# onduleur.net
KiCad netlist of a schematic drawn in Altium Designer
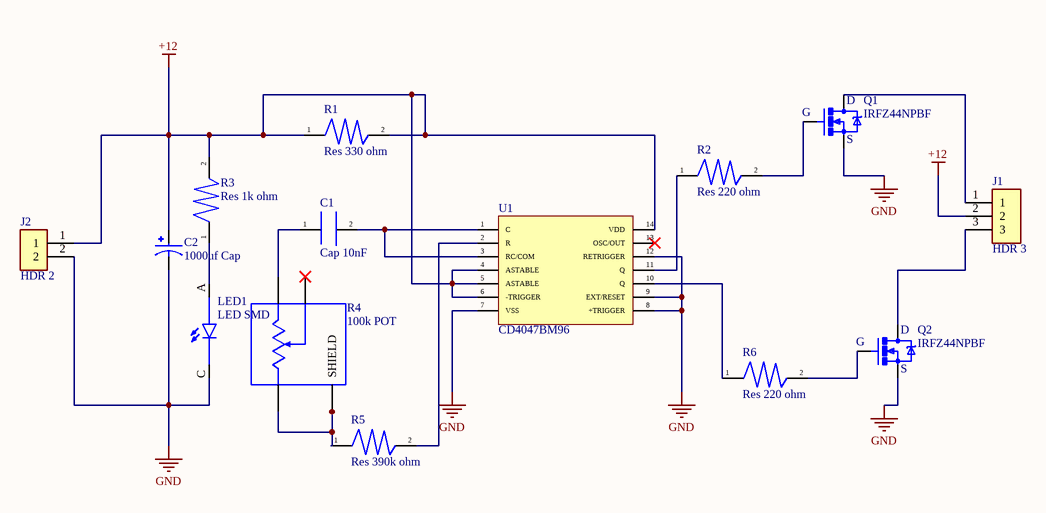
[diagram p0: onduleur.SchDoc]

(export (version "E")
  (design (tool "Eeschema 10.0.6"))
  (components
    (comp (ref "C1")
      (value "Cap 10nF")
      (footprint "C0805 10nf")
      (description "0805 330 nF 25 V -20 / +80 % Tolerance Y5V SMT Multilayer Ceramic Capacitor")
      (fields
        (field (name "MANUFACTURER") "Kyocera AVX")
        (field (name "MANUFACTURER PART NUMBER") "08053G334ZAT2A")
      )
      (libsource (lib "ONDULEUR") (part "Cap 10nF"))
    )
    (comp (ref "C2")
      (value "1000uf Cap")
      (footprint "Cap 1000uf")
      (description "Cap Aluminum 1000uF 50V 20% (12.5 X 25mm) Radial 5mm 950mA 2000 hr 105°C Ammo Pack")
      (fields
        (field (name "MANUFACTURER") "Panasonic")
        (field (name "MANUFACTURER PART NUMBER") "EEU-HD1H102B")
      )
      (libsource (lib "ONDULEUR") (part "1000uf Cap"))
    )
    (comp (ref "J1")
      (value "HDR 3")
      (footprint "HDR 3")
      (description "3 Position Wire to Board Terminal Block Horizontal with Board 0.150\" (3.81mm) Through Hole")
      (fields
        (field (name "MANUFACTURER") "TE Connectivity")
        (field (name "MANUFACTURER PART NUMBER") "284392-3")
      )
      (libsource (lib "ONDULEUR") (part "HDR 3"))
    )
    (comp (ref "J2")
      (value "HDR 2")
      (footprint "HDR 2")
      (description "Conn Terminal Block 2 POS 5.08mm Solder ST Thru-Hole 17.5A/Contact")
      (fields
        (field (name "MANUFACTURER") "TE Connectivity")
        (field (name "MANUFACTURER PART NUMBER") "282841-2")
      )
      (libsource (lib "ONDULEUR") (part "HDR 2"))
    )
    (comp (ref "LED1")
      (value "LED SMD")
      (footprint "LED")
      (description "LED RED CLEAR 1206 SMD")
      (fields
        (field (name "MANUFACTURER") "Vishay Lite-On")
        (field (name "MANUFACTURER PART NUMBER") "LTST-C230KRKT")
      )
      (libsource (lib "ONDULEUR") (part "LED SMD"))
    )
    (comp (ref "Q1")
      (value "IRFZ44NPBF")
      (footprint "IRF")
      (description "N沟道 VDS=55V VGS=±20V ID=49A")
      (fields (field (name "MANUFACTURER") "Infineon"))
      (libsource (lib "ONDULEUR") (part "IRFZ44NPBF"))
    )
    (comp (ref "Q2")
      (value "IRFZ44NPBF")
      (footprint "IRF")
      (description "N沟道 VDS=55V VGS=±20V ID=49A")
      (fields (field (name "MANUFACTURER") "Infineon"))
      (libsource (lib "ONDULEUR") (part "IRFZ44NPBF"))
    )
    (comp (ref "R1")
      (value "Res 330 ohm")
      (footprint "R2010 330 ohm")
      (description "Res Thick Film 2010 330 Ohm 1% 1W ±100ppm/°C Molded SMD SMD Paper T/R")
      (fields
        (field (name "MANUFACTURER") "Stackpole Electronics")
        (field (name "MANUFACTURER PART NUMBER") "RMCP2010FT330R")
      )
      (libsource (lib "ONDULEUR") (part "Res 330 ohm"))
    )
    (comp (ref "R2")
      (value "Res 220 ohm")
      (footprint "R2512 220ohm")
      (description "Res Thick Film 2512 220 Ohm 1% 1W ±100ppm/°C Pad SMD T/R")
      (fields
        (field (name "MANUFACTURER") "Yageo")
        (field (name "MANUFACTURER PART NUMBER") "RC2512FK-07220RL")
      )
      (libsource (lib "ONDULEUR") (part "Res 220 ohm"))
    )
    (comp (ref "R3")
      (value "Res 1k ohm")
      (footprint "R2512 390k")
      (description "贴片电阻 1KΩ 1KΩ ±5% 1W 2512")
      (fields
        (field (name "MANUFACTURER") "Yageo")
        (field (name "MANUFACTURER PART NUMBER") "RC2512JK-071KL")
      )
      (libsource (lib "ONDULEUR") (part "Res 1k ohm"))
    )
    (comp (ref "R4")
      (value "100k POT")
      (footprint "100k POt")
      (fields
        (field (name "MANUFACTURER") "TT BI")
        (field (name "MANUFACTURER PART NUMBER") "P0915N-FC15BR100K")
        (field (name "TOLERANCE") "20%")
      )
      (libsource (lib "ONDULEUR") (part "100k POT"))
    )
    (comp (ref "R5")
      (value "Res 390k ohm")
      (footprint "R2512 390k")
      (description "Res Thick Film 2512 390K Ohm 5% 1W ±200ppm/°C Molded SMD Embossed Carrier T/R")
      (fields
        (field (name "MANUFACTURER") "Panasonic")
        (field (name "MANUFACTURER PART NUMBER") "ERJ-1TYJ394U")
      )
      (libsource (lib "ONDULEUR") (part "Res 390k ohm"))
    )
    (comp (ref "R6")
      (value "Res 220 ohm")
      (footprint "R2512 220ohm")
      (description "Res Thick Film 2512 220 Ohm 1% 1W ±100ppm/°C Pad SMD T/R")
      (fields
        (field (name "MANUFACTURER") "Yageo")
        (field (name "MANUFACTURER PART NUMBER") "RC2512FK-07220RL")
      )
      (libsource (lib "ONDULEUR") (part "Res 220 ohm"))
    )
    (comp (ref "U1")
      (value "CD4047BM96")
      (footprint "CD4047_SOP14")
      (description "IC MONO/ASTBL MULTVIBRTR 14SOIC")
      (fields (field (name "MANUFACTURER") "Texas Instruments"))
      (libsource (lib "ONDULEUR") (part "CD4047BM96"))
    )
  )
  (nets
    (net (code "1") (name "+12") (class "Default")
      (node (ref "C2") (pin "P") (pinfunction "P_P") (pintype "passive"))
      (node (ref "J1") (pin "2") (pinfunction "2_2") (pintype "passive"))
      (node (ref "J2") (pin "1") (pinfunction "1_1") (pintype "passive"))
      (node (ref "R1") (pin "1") (pinfunction "1_1") (pintype "passive"))
      (node (ref "R1") (pin "2") (pinfunction "2_2") (pintype "passive"))
      (node (ref "R3") (pin "2") (pinfunction "2_2") (pintype "passive"))
      (node (ref "U1") (pin "14") (pinfunction "VDD_14") (pintype "passive"))
      (node (ref "U1") (pin "4") (pinfunction "ASTABLE_4") (pintype "passive"))
      (node (ref "U1") (pin "5") (pinfunction "ASTABLE_5") (pintype "passive"))
      (node (ref "U1") (pin "6") (pinfunction "-TRIGGER_6") (pintype "passive"))
    )
    (net (code "2") (name "GND") (class "Default")
      (node (ref "C2") (pin "N") (pinfunction "N_N") (pintype "passive"))
      (node (ref "J2") (pin "2") (pinfunction "2_2") (pintype "passive"))
      (node (ref "LED1") (pin "C") (pinfunction "C_C") (pintype "passive"))
      (node (ref "Q1") (pin "3") (pinfunction "S_3") (pintype "passive"))
      (node (ref "Q2") (pin "3") (pinfunction "S_3") (pintype "passive"))
      (node (ref "U1") (pin "12") (pinfunction "RETRIGGER_12") (pintype "passive"))
      (node (ref "U1") (pin "7") (pinfunction "VSS_7") (pintype "passive"))
      (node (ref "U1") (pin "8") (pinfunction "+TRIGGER_8") (pintype "passive"))
      (node (ref "U1") (pin "9") (pinfunction "EXT/RESET_9") (pintype "passive"))
    )
    (net (code "3") (name "Net-(C1-18)") (class "Default")
      (node (ref "C1") (pin "1") (pinfunction "18_1") (pintype "passive"))
      (node (ref "R4") (pin "3") (pinfunction "3_3") (pintype "passive"))
    )
    (net (code "4") (name "Net-(C1-19)") (class "Default")
      (node (ref "C1") (pin "2") (pinfunction "19_2") (pintype "passive"))
      (node (ref "U1") (pin "1") (pinfunction "C_1") (pintype "passive"))
      (node (ref "U1") (pin "3") (pinfunction "RC/COM_3") (pintype "passive"))
    )
    (net (code "5") (name "Net-(LED1-PadA)") (class "Default")
      (node (ref "LED1") (pin "A") (pinfunction "A_A") (pintype "passive"))
      (node (ref "R3") (pin "1") (pinfunction "1_1") (pintype "passive"))
    )
    (net (code "6") (name "Net-(Q1-D)") (class "Default")
      (node (ref "J1") (pin "1") (pinfunction "1_1") (pintype "passive"))
      (node (ref "Q1") (pin "2") (pinfunction "D_2") (pintype "passive"))
    )
    (net (code "7") (name "Net-(Q1-G)") (class "Default")
      (node (ref "Q1") (pin "1") (pinfunction "G_1") (pintype "passive"))
      (node (ref "R2") (pin "2") (pinfunction "2_2") (pintype "passive"))
    )
    (net (code "8") (name "Net-(Q2-D)") (class "Default")
      (node (ref "J1") (pin "3") (pinfunction "3_3") (pintype "passive"))
      (node (ref "Q2") (pin "2") (pinfunction "D_2") (pintype "passive"))
    )
    (net (code "9") (name "Net-(Q2-G)") (class "Default")
      (node (ref "Q2") (pin "1") (pinfunction "G_1") (pintype "passive"))
      (node (ref "R6") (pin "2") (pinfunction "2_2") (pintype "passive"))
    )
    (net (code "10") (name "Net-(R2-Pad1)") (class "Default")
      (node (ref "R2") (pin "1") (pinfunction "1_1") (pintype "passive"))
      (node (ref "U1") (pin "11") (pinfunction "Q_11") (pintype "passive"))
    )
    (net (code "11") (name "Net-(R4-Pad1)") (class "Default")
      (node (ref "R4") (pin "1") (pinfunction "1_1") (pintype "passive"))
      (node (ref "R4") (pin "S1") (pinfunction "SHIELD_S1") (pintype "passive"))
      (node (ref "R4") (pin "S2") (pinfunction "SHIELD_S2") (pintype "passive"))
      (node (ref "R5") (pin "1") (pinfunction "1_1") (pintype "passive"))
    )
    (net (code "12") (name "Net-(R6-Pad1)") (class "Default")
      (node (ref "R6") (pin "1") (pinfunction "1_1") (pintype "passive"))
      (node (ref "U1") (pin "10") (pinfunction "Q_10") (pintype "passive"))
    )
    (net (code "13") (name "Net-(U1-R)") (class "Default")
      (node (ref "R5") (pin "2") (pinfunction "2_2") (pintype "passive"))
      (node (ref "U1") (pin "2") (pinfunction "R_2") (pintype "passive"))
    )
    (net (code "14") (name "unconnected-(R4-Pad2)") (class "Default")
      (node (ref "R4") (pin "2") (pinfunction "2_2") (pintype "passive+no_connect"))
    )
    (net (code "15") (name "unconnected-(U1-OSC{slash}OUT-Pad13)") (class "Default")
      (node (ref "U1") (pin "13") (pinfunction "OSC/OUT_13") (pintype "passive+no_connect"))
    )
  )
)
